# bt_adapter.net
KiCad netlist of a schematic drawn in EAGLE
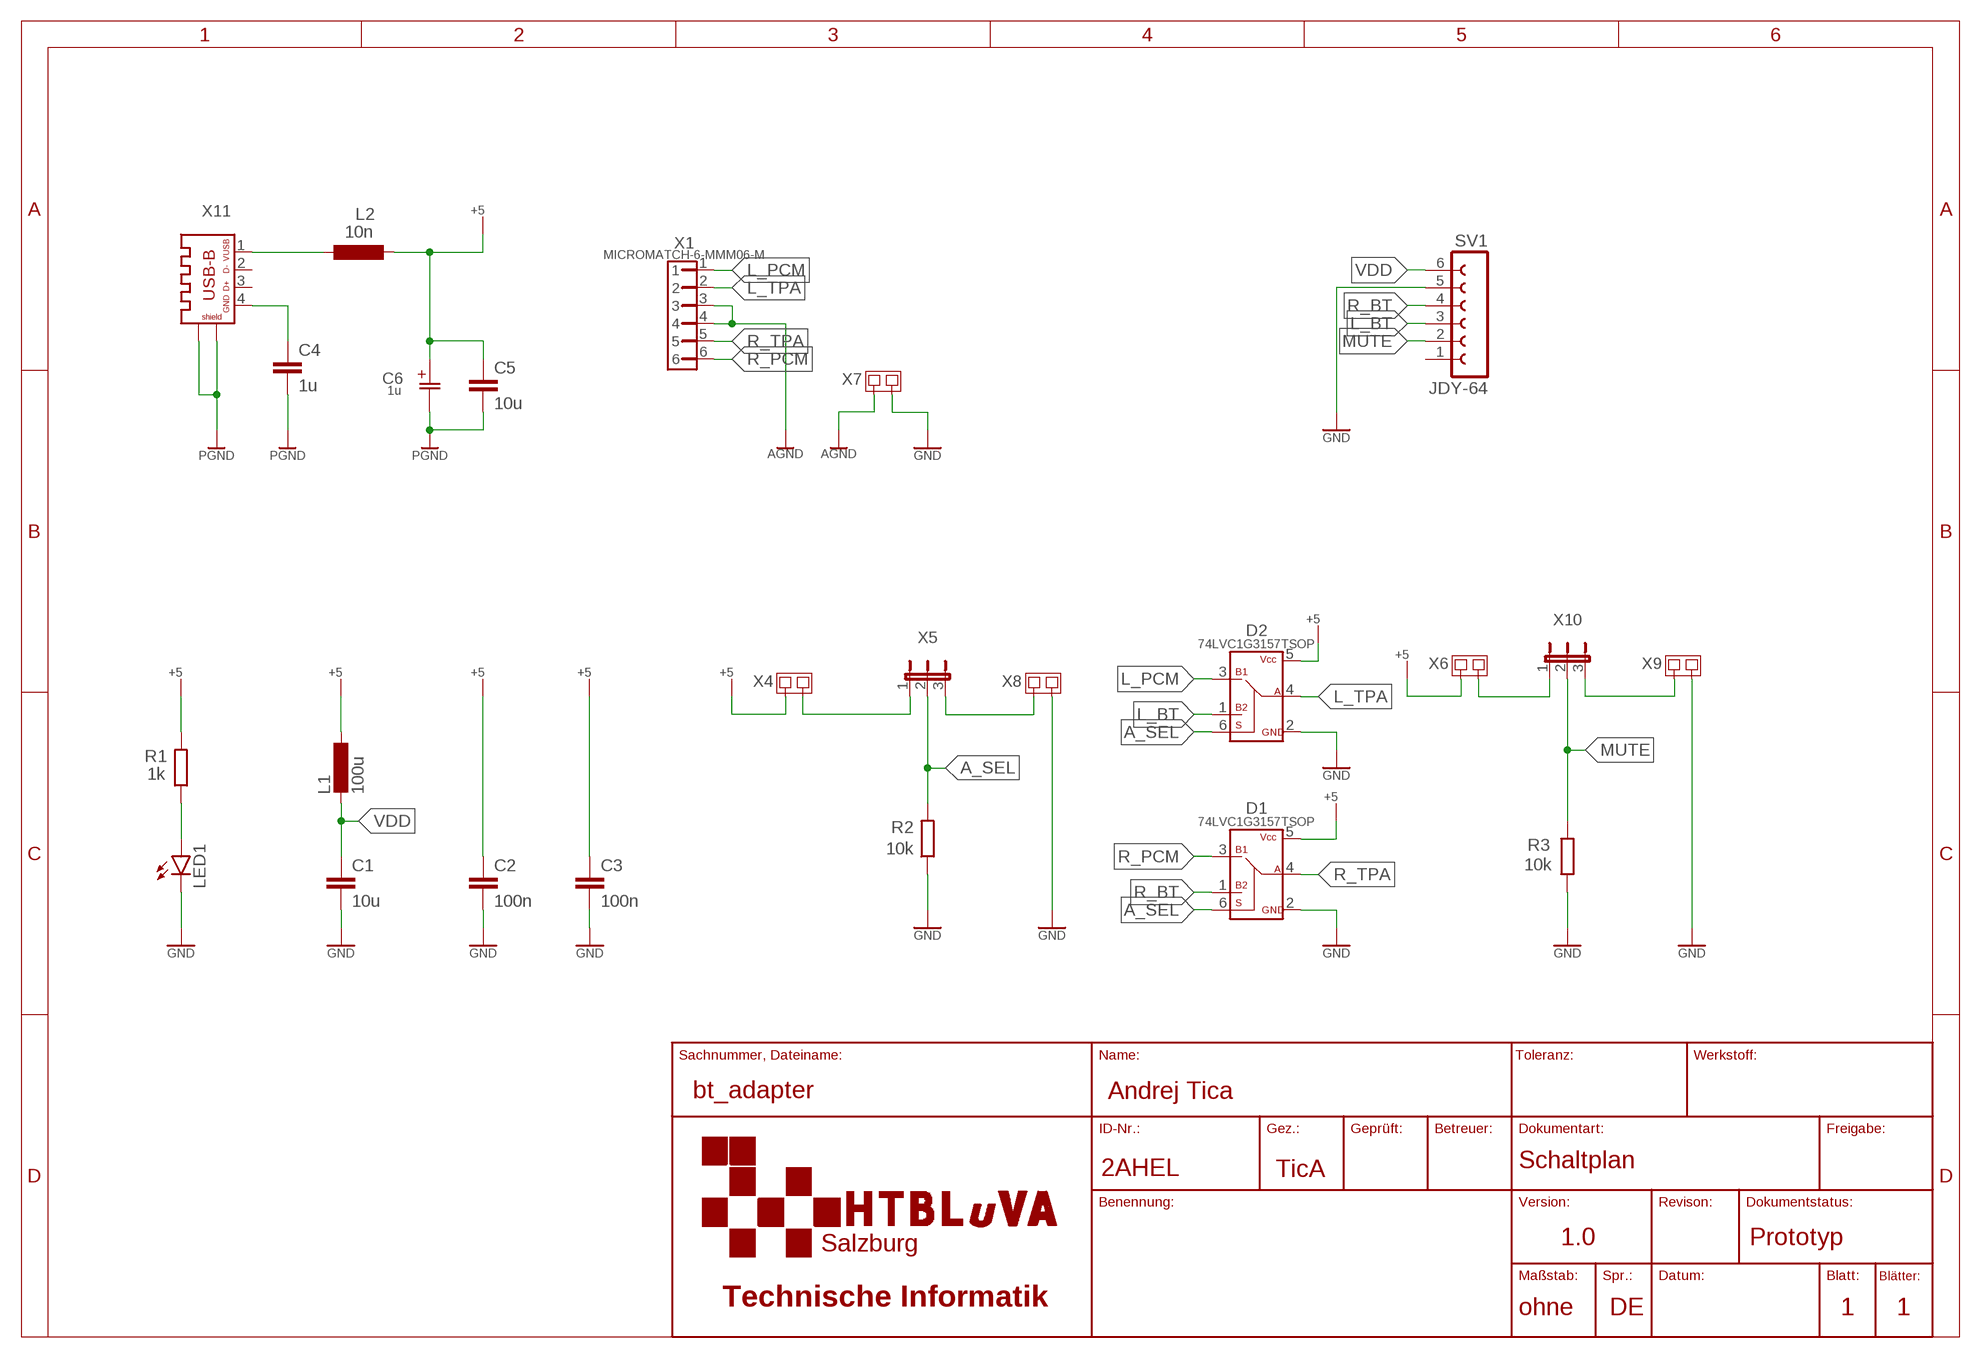
[diagram p0: schematic, sheet 1]

(export (version "E")
  (design (tool "Eeschema 10.0.6"))
  (components
    (comp (ref "C1")
      (value "10u")
      (footprint "eagle-import:C025-025X050")
      (libsource (lib "eagle-import") (part "C-EU025-025X050"))
    )
    (comp (ref "C2")
      (value "100n")
      (footprint "eagle-import:C025-025X050")
      (libsource (lib "eagle-import") (part "C-EU025-025X050"))
    )
    (comp (ref "C3")
      (value "100n")
      (footprint "eagle-import:C025-025X050")
      (libsource (lib "eagle-import") (part "C-EU025-025X050"))
    )
    (comp (ref "C4")
      (value "1u")
      (footprint "eagle-import:C3216")
      (libsource (lib "eagle-import") (part "C-EUC3216"))
    )
    (comp (ref "C5")
      (value "10u")
      (footprint "eagle-import:C3216")
      (libsource (lib "eagle-import") (part "C-EUC3216"))
    )
    (comp (ref "C6")
      (value "1u")
      (footprint "eagle-import:MYLIB_C3216")
      (libsource (lib "eagle-import") (part "CPOL-EU3216"))
    )
    (comp (ref "D1")
      (value "74LVC1G3157TSOP")
      (footprint "eagle-import:TSOP6")
      (libsource (lib "eagle-import") (part "74LVC1G3157TSOP"))
    )
    (comp (ref "D2")
      (value "74LVC1G3157TSOP")
      (footprint "eagle-import:TSOP6")
      (libsource (lib "eagle-import") (part "74LVC1G3157TSOP"))
    )
    (comp (ref "L1")
      (value "100u")
      (footprint "eagle-import:0204_7")
      (libsource (lib "eagle-import") (part "L-EU0204/7"))
    )
    (comp (ref "L2")
      (value "10n")
      (footprint "eagle-import:0204_7")
      (libsource (lib "eagle-import") (part "L-EU0204/7"))
    )
    (comp (ref "LED1")
      (value "LED5MM")
      (footprint "eagle-import:LED5MM")
      (libsource (lib "eagle-import") (part "LED5MM"))
    )
    (comp (ref "R1")
      (value "1k")
      (footprint "eagle-import:0204_7")
      (libsource (lib "eagle-import") (part "R-EU_0204/7"))
    )
    (comp (ref "R2")
      (value "10k")
      (footprint "eagle-import:0204_7")
      (libsource (lib "eagle-import") (part "R-EU_0204/7"))
    )
    (comp (ref "R3")
      (value "10k")
      (footprint "eagle-import:0204_7")
      (libsource (lib "eagle-import") (part "R-EU_0204/7"))
    )
    (comp (ref "SV1")
      (value "JDY-64")
      (footprint "eagle-import:FE06")
      (libsource (lib "eagle-import") (part "FE06-1"))
    )
    (comp (ref "X1")
      (value "MICROMATCH-6-MMM06-M")
      (footprint "eagle-import:MICROMATCH-06-W-M")
      (libsource (lib "eagle-import") (part "MICROMATCH-6-MMM06-M"))
    )
    (comp (ref "X4")
      (value "JUMPSMD1FACH")
      (footprint "eagle-import:VERSTäRKER_SJ")
      (libsource (lib "eagle-import") (part "JUMPSMD1FACH"))
    )
    (comp (ref "X5")
      (value "JUMPER_JP3EJP3E")
      (footprint "eagle-import:JUMPER_JP3")
      (libsource (lib "eagle-import") (part "JUMPER_JP3EJP3E"))
    )
    (comp (ref "X6")
      (value "JUMPSMD1FACH")
      (footprint "eagle-import:VERSTäRKER_SJ")
      (libsource (lib "eagle-import") (part "JUMPSMD1FACH"))
    )
    (comp (ref "X7")
      (value "JUMPSMD1FACH")
      (footprint "eagle-import:VERSTäRKER_SJ")
      (libsource (lib "eagle-import") (part "JUMPSMD1FACH"))
    )
    (comp (ref "X8")
      (value "JUMPSMD1FACH")
      (footprint "eagle-import:VERSTäRKER_SJ")
      (libsource (lib "eagle-import") (part "JUMPSMD1FACH"))
    )
    (comp (ref "X9")
      (value "JUMPSMD1FACH")
      (footprint "eagle-import:VERSTäRKER_SJ")
      (libsource (lib "eagle-import") (part "JUMPSMD1FACH"))
    )
    (comp (ref "X10")
      (value "JUMPER_JP3EJP3E")
      (footprint "eagle-import:JUMPER_JP3")
      (libsource (lib "eagle-import") (part "JUMPER_JP3EJP3E"))
    )
    (comp (ref "X11")
      (value "USB-B-12411")
      (footprint "eagle-import:MYLIB_USB-B-LUM")
      (libsource (lib "eagle-import") (part "USB-B-12411"))
    )
  )
  (nets
    (net (code "1") (name "+5") (class "Default")
      (node (ref "C2") (pin "1") (pinfunction "1_1") (pintype "passive"))
      (node (ref "C3") (pin "1") (pinfunction "1_1") (pintype "passive"))
      (node (ref "C5") (pin "1") (pinfunction "1_1") (pintype "passive"))
      (node (ref "C6") (pin "2") (pinfunction "+_2") (pintype "passive"))
      (node (ref "D1") (pin "5") (pinfunction "VCC_5") (pintype "bidirectional"))
      (node (ref "D2") (pin "5") (pinfunction "VCC_5") (pintype "bidirectional"))
      (node (ref "L1") (pin "1") (pinfunction "1_1") (pintype "passive"))
      (node (ref "L2") (pin "2") (pinfunction "2_2") (pintype "passive"))
      (node (ref "R1") (pin "2") (pinfunction "2_2") (pintype "passive"))
      (node (ref "X4") (pin "1") (pinfunction "1_1") (pintype "passive"))
      (node (ref "X6") (pin "1") (pinfunction "1_1") (pintype "passive"))
    )
    (net (code "2") (name "AGND") (class "Default")
      (node (ref "X1") (pin "3") (pinfunction "3_3") (pintype "passive"))
      (node (ref "X1") (pin "4") (pinfunction "4_4") (pintype "passive"))
      (node (ref "X7") (pin "1") (pinfunction "1_1") (pintype "passive"))
    )
    (net (code "3") (name "A_SEL") (class "Default")
      (node (ref "D1") (pin "6") (pinfunction "S_6") (pintype "bidirectional"))
      (node (ref "D2") (pin "6") (pinfunction "S_6") (pintype "bidirectional"))
      (node (ref "R2") (pin "2") (pinfunction "2_2") (pintype "passive"))
      (node (ref "X5") (pin "2") (pinfunction "2_2") (pintype "passive"))
    )
    (net (code "4") (name "GND") (class "Default")
      (node (ref "C1") (pin "2") (pinfunction "2_2") (pintype "passive"))
      (node (ref "C2") (pin "2") (pinfunction "2_2") (pintype "passive"))
      (node (ref "C3") (pin "2") (pinfunction "2_2") (pintype "passive"))
      (node (ref "D1") (pin "2") (pinfunction "GND_2") (pintype "bidirectional"))
      (node (ref "D2") (pin "2") (pinfunction "GND_2") (pintype "bidirectional"))
      (node (ref "LED1") (pin "K") (pinfunction "C_K") (pintype "passive"))
      (node (ref "R2") (pin "1") (pinfunction "1_1") (pintype "passive"))
      (node (ref "R3") (pin "1") (pinfunction "1_1") (pintype "passive"))
      (node (ref "SV1") (pin "5") (pinfunction "5_5") (pintype "passive"))
      (node (ref "X7") (pin "2") (pinfunction "2_2") (pintype "passive"))
      (node (ref "X8") (pin "2") (pinfunction "2_2") (pintype "passive"))
      (node (ref "X9") (pin "2") (pinfunction "2_2") (pintype "passive"))
    )
    (net (code "5") (name "L_BT") (class "Default")
      (node (ref "D2") (pin "1") (pinfunction "B2_1") (pintype "bidirectional"))
      (node (ref "SV1") (pin "3") (pinfunction "3_3") (pintype "passive"))
    )
    (net (code "6") (name "L_PCM") (class "Default")
      (node (ref "D2") (pin "3") (pinfunction "B1_3") (pintype "bidirectional"))
      (node (ref "X1") (pin "1") (pinfunction "1_1") (pintype "passive"))
    )
    (net (code "7") (name "L_TPA") (class "Default")
      (node (ref "D2") (pin "4") (pinfunction "A_4") (pintype "bidirectional"))
      (node (ref "X1") (pin "2") (pinfunction "2_2") (pintype "passive"))
    )
    (net (code "8") (name "MUTE") (class "Default")
      (node (ref "R3") (pin "2") (pinfunction "2_2") (pintype "passive"))
      (node (ref "SV1") (pin "2") (pinfunction "2_2") (pintype "passive"))
      (node (ref "X10") (pin "2") (pinfunction "2_2") (pintype "passive"))
    )
    (net (code "9") (name "Net-(C4-Pad1)") (class "Default")
      (node (ref "C4") (pin "1") (pinfunction "1_1") (pintype "passive"))
      (node (ref "X11") (pin "4") (pinfunction "4_4") (pintype "passive"))
    )
    (net (code "10") (name "Net-(L2-Pad1)") (class "Default")
      (node (ref "L2") (pin "1") (pinfunction "1_1") (pintype "passive"))
      (node (ref "X11") (pin "1") (pinfunction "1_1") (pintype "passive"))
    )
    (net (code "11") (name "Net-(LED1-PadA)") (class "Default")
      (node (ref "LED1") (pin "A") (pinfunction "A_A") (pintype "passive"))
      (node (ref "R1") (pin "1") (pinfunction "1_1") (pintype "passive"))
    )
    (net (code "12") (name "Net-(X4-Pad2)") (class "Default")
      (node (ref "X4") (pin "2") (pinfunction "2_2") (pintype "passive"))
      (node (ref "X5") (pin "1") (pinfunction "1_1") (pintype "passive"))
    )
    (net (code "13") (name "Net-(X5-Pad3)") (class "Default")
      (node (ref "X5") (pin "3") (pinfunction "3_3") (pintype "passive"))
      (node (ref "X8") (pin "1") (pinfunction "1_1") (pintype "passive"))
    )
    (net (code "14") (name "Net-(X10-Pad1)") (class "Default")
      (node (ref "X10") (pin "1") (pinfunction "1_1") (pintype "passive"))
      (node (ref "X6") (pin "2") (pinfunction "2_2") (pintype "passive"))
    )
    (net (code "15") (name "Net-(X10-Pad3)") (class "Default")
      (node (ref "X10") (pin "3") (pinfunction "3_3") (pintype "passive"))
      (node (ref "X9") (pin "1") (pinfunction "1_1") (pintype "passive"))
    )
    (net (code "16") (name "PGND") (class "Default")
      (node (ref "C4") (pin "2") (pinfunction "2_2") (pintype "passive"))
      (node (ref "C5") (pin "2") (pinfunction "2_2") (pintype "passive"))
      (node (ref "C6") (pin "1") (pinfunction "-_1") (pintype "passive"))
      (node (ref "X11") (pin "SH@1") (pinfunction "SH1_SH@1") (pintype "passive"))
      (node (ref "X11") (pin "SH@2") (pinfunction "SH2_SH@2") (pintype "passive"))
    )
    (net (code "17") (name "R_BT") (class "Default")
      (node (ref "D1") (pin "1") (pinfunction "B2_1") (pintype "bidirectional"))
      (node (ref "SV1") (pin "4") (pinfunction "4_4") (pintype "passive"))
    )
    (net (code "18") (name "R_PCM") (class "Default")
      (node (ref "D1") (pin "3") (pinfunction "B1_3") (pintype "bidirectional"))
      (node (ref "X1") (pin "6") (pinfunction "6_6") (pintype "passive"))
    )
    (net (code "19") (name "R_TPA") (class "Default")
      (node (ref "D1") (pin "4") (pinfunction "A_4") (pintype "bidirectional"))
      (node (ref "X1") (pin "5") (pinfunction "5_5") (pintype "passive"))
    )
    (net (code "20") (name "VDD") (class "Default")
      (node (ref "C1") (pin "1") (pinfunction "1_1") (pintype "passive"))
      (node (ref "L1") (pin "2") (pinfunction "2_2") (pintype "passive"))
      (node (ref "SV1") (pin "6") (pinfunction "6_6") (pintype "passive"))
    )
    (net (code "21") (name "unconnected-(SV1-Pad1)") (class "Default")
      (node (ref "SV1") (pin "1") (pinfunction "1_1") (pintype "passive"))
    )
    (net (code "22") (name "unconnected-(X11-Pad2)") (class "Default")
      (node (ref "X11") (pin "2") (pinfunction "2_2") (pintype "passive"))
    )
    (net (code "23") (name "unconnected-(X11-Pad3)") (class "Default")
      (node (ref "X11") (pin "3") (pinfunction "3_3") (pintype "passive"))
    )
  )
)
